# Relay-Board_Rack-PDU.net
KiCad netlist of a schematic drawn in EAGLE
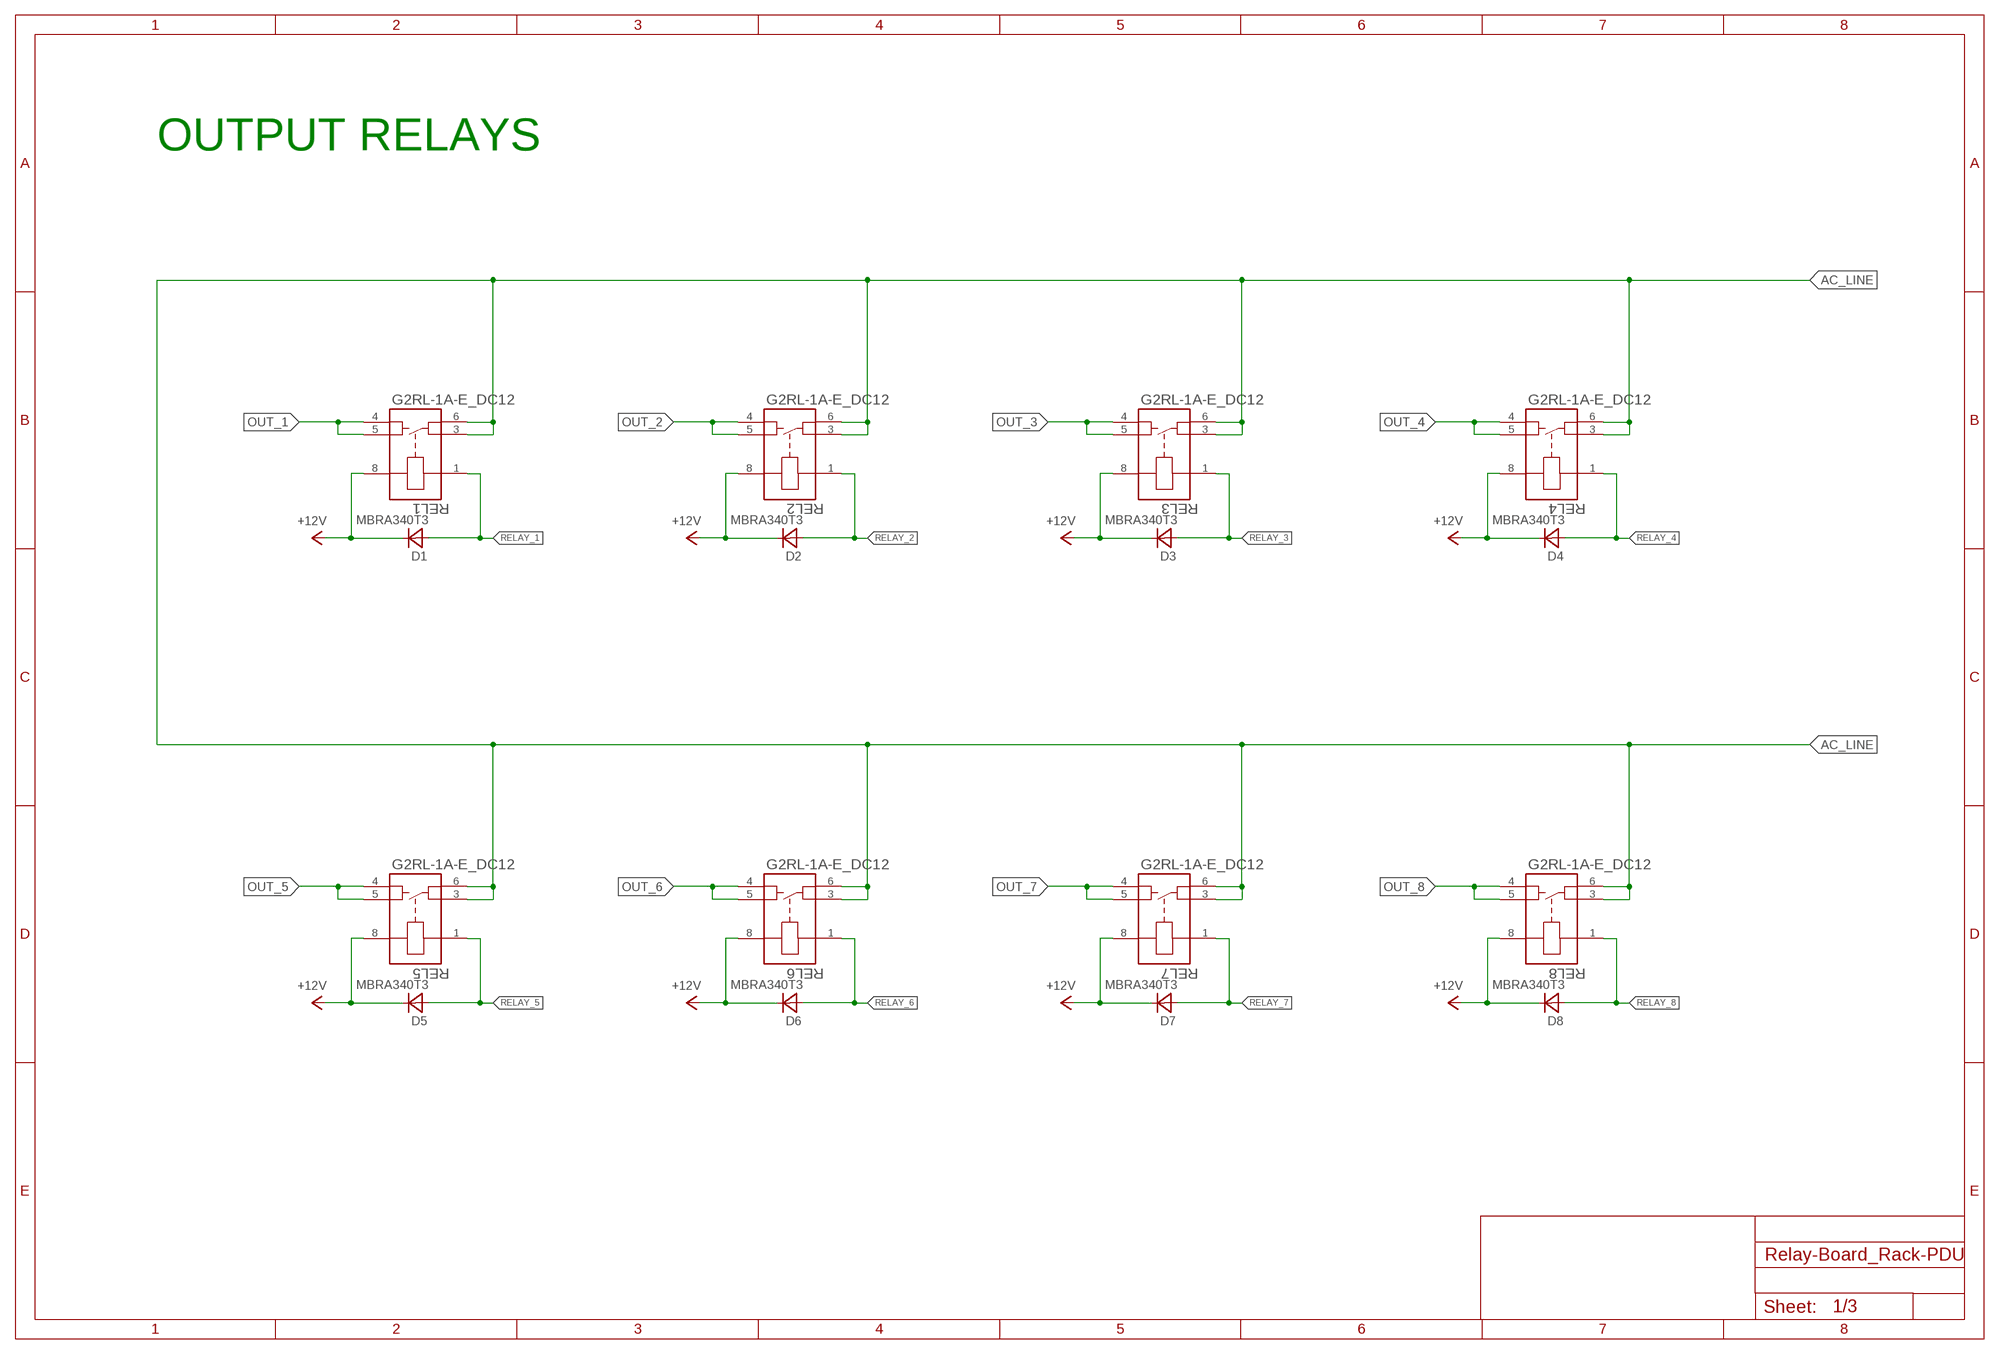
[diagram p0: schematic, sheet 1]
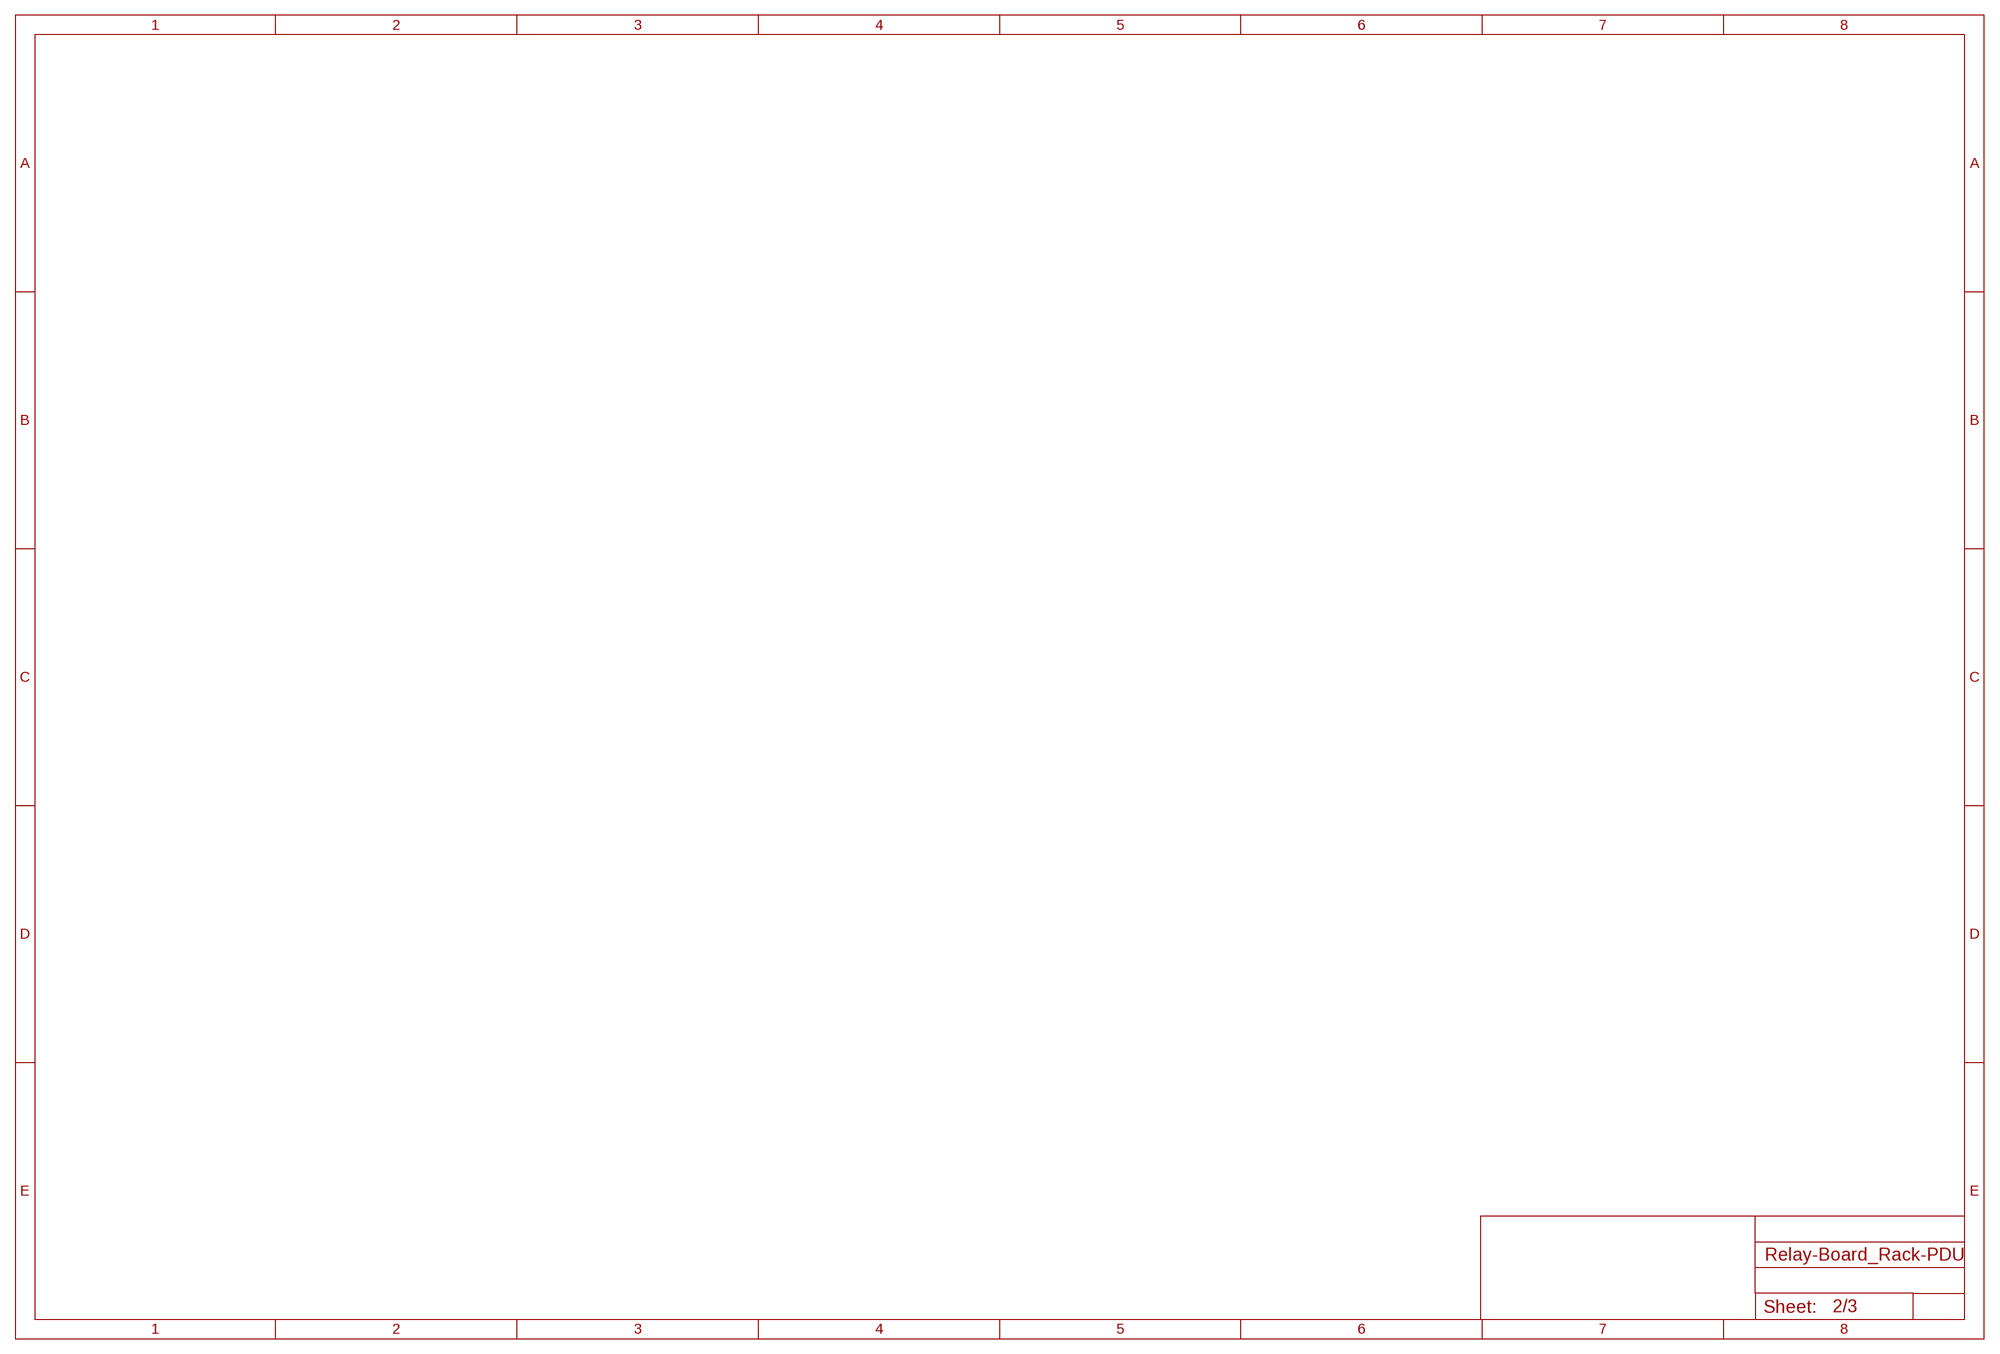
[diagram p1: schematic, sheet 2]
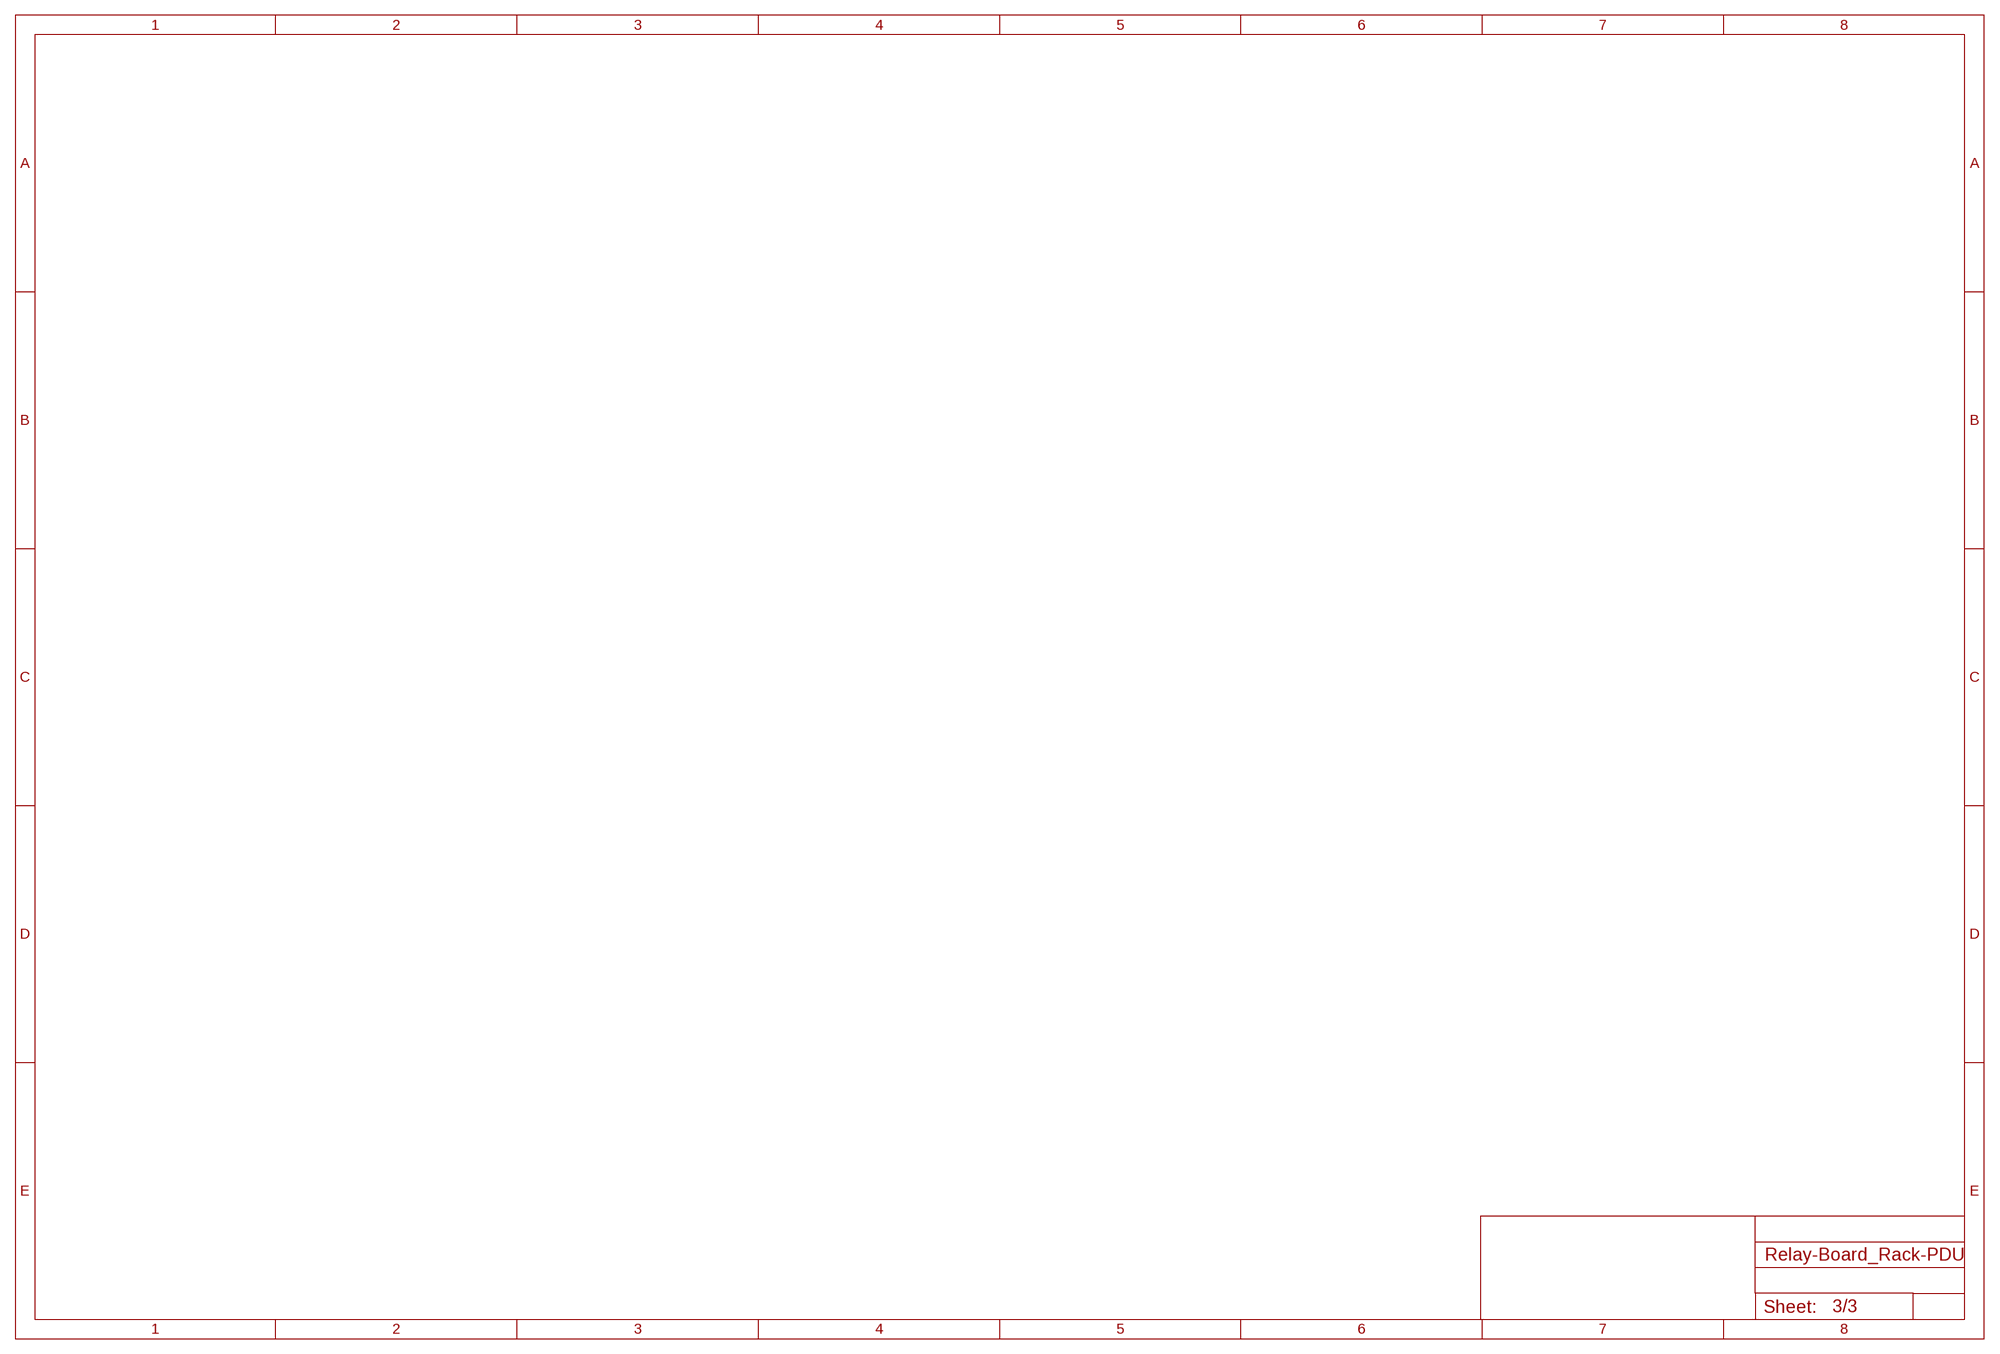
[diagram p2: schematic, sheet 3]

(export (version "E")
  (design (tool "Eeschema 10.0.6"))
  (components
    (comp (ref "D1")
      (value "MBRA340T3")
      (footprint "eagle-import:SMA")
      (libsource (lib "eagle-import") (part "MBRA340T3"))
    )
    (comp (ref "D2")
      (value "MBRA340T3")
      (footprint "eagle-import:SMA")
      (libsource (lib "eagle-import") (part "MBRA340T3"))
    )
    (comp (ref "D3")
      (value "MBRA340T3")
      (footprint "eagle-import:SMA")
      (libsource (lib "eagle-import") (part "MBRA340T3"))
    )
    (comp (ref "D4")
      (value "MBRA340T3")
      (footprint "eagle-import:SMA")
      (libsource (lib "eagle-import") (part "MBRA340T3"))
    )
    (comp (ref "D5")
      (value "MBRA340T3")
      (footprint "eagle-import:SMA")
      (libsource (lib "eagle-import") (part "MBRA340T3"))
    )
    (comp (ref "D6")
      (value "MBRA340T3")
      (footprint "eagle-import:SMA")
      (libsource (lib "eagle-import") (part "MBRA340T3"))
    )
    (comp (ref "D7")
      (value "MBRA340T3")
      (footprint "eagle-import:SMA")
      (libsource (lib "eagle-import") (part "MBRA340T3"))
    )
    (comp (ref "D8")
      (value "MBRA340T3")
      (footprint "eagle-import:SMA")
      (libsource (lib "eagle-import") (part "MBRA340T3"))
    )
    (comp (ref "REL1")
      (value "G2RL-1A-E_DC12")
      (footprint "eagle-import:RELAY_G2RL-1A-E_DC5_OMR")
      (fields
        (field (name "MANUFACTURER_PART_NUMBER") "G2RL-1A-E DC12")
        (field (name "COPYRIGHT") "Copyright (C) 2025 Ultra Librarian. All rights reserved.")
      )
      (libsource (lib "eagle-import") (part "G2RL-1A-E_DC12"))
    )
    (comp (ref "REL2")
      (value "G2RL-1A-E_DC12")
      (footprint "eagle-import:RELAY_G2RL-1A-E_DC5_OMR")
      (fields
        (field (name "MANUFACTURER_PART_NUMBER") "G2RL-1A-E DC12")
        (field (name "COPYRIGHT") "Copyright (C) 2025 Ultra Librarian. All rights reserved.")
      )
      (libsource (lib "eagle-import") (part "G2RL-1A-E_DC12"))
    )
    (comp (ref "REL3")
      (value "G2RL-1A-E_DC12")
      (footprint "eagle-import:RELAY_G2RL-1A-E_DC5_OMR")
      (fields
        (field (name "MANUFACTURER_PART_NUMBER") "G2RL-1A-E DC12")
        (field (name "COPYRIGHT") "Copyright (C) 2025 Ultra Librarian. All rights reserved.")
      )
      (libsource (lib "eagle-import") (part "G2RL-1A-E_DC12"))
    )
    (comp (ref "REL4")
      (value "G2RL-1A-E_DC12")
      (footprint "eagle-import:RELAY_G2RL-1A-E_DC5_OMR")
      (fields
        (field (name "MANUFACTURER_PART_NUMBER") "G2RL-1A-E DC12")
        (field (name "COPYRIGHT") "Copyright (C) 2025 Ultra Librarian. All rights reserved.")
      )
      (libsource (lib "eagle-import") (part "G2RL-1A-E_DC12"))
    )
    (comp (ref "REL5")
      (value "G2RL-1A-E_DC12")
      (footprint "eagle-import:RELAY_G2RL-1A-E_DC5_OMR")
      (fields
        (field (name "MANUFACTURER_PART_NUMBER") "G2RL-1A-E DC12")
        (field (name "COPYRIGHT") "Copyright (C) 2025 Ultra Librarian. All rights reserved.")
      )
      (libsource (lib "eagle-import") (part "G2RL-1A-E_DC12"))
    )
    (comp (ref "REL6")
      (value "G2RL-1A-E_DC12")
      (footprint "eagle-import:RELAY_G2RL-1A-E_DC5_OMR")
      (fields
        (field (name "MANUFACTURER_PART_NUMBER") "G2RL-1A-E DC12")
        (field (name "COPYRIGHT") "Copyright (C) 2025 Ultra Librarian. All rights reserved.")
      )
      (libsource (lib "eagle-import") (part "G2RL-1A-E_DC12"))
    )
    (comp (ref "REL7")
      (value "G2RL-1A-E_DC12")
      (footprint "eagle-import:RELAY_G2RL-1A-E_DC5_OMR")
      (fields
        (field (name "MANUFACTURER_PART_NUMBER") "G2RL-1A-E DC12")
        (field (name "COPYRIGHT") "Copyright (C) 2025 Ultra Librarian. All rights reserved.")
      )
      (libsource (lib "eagle-import") (part "G2RL-1A-E_DC12"))
    )
    (comp (ref "REL8")
      (value "G2RL-1A-E_DC12")
      (footprint "eagle-import:RELAY_G2RL-1A-E_DC5_OMR")
      (fields
        (field (name "MANUFACTURER_PART_NUMBER") "G2RL-1A-E DC12")
        (field (name "COPYRIGHT") "Copyright (C) 2025 Ultra Librarian. All rights reserved.")
      )
      (libsource (lib "eagle-import") (part "G2RL-1A-E_DC12"))
    )
  )
  (nets
    (net (code "1") (name "+12V") (class "Default")
      (node (ref "D1") (pin "C") (pinfunction "C_C") (pintype "passive"))
      (node (ref "D2") (pin "C") (pinfunction "C_C") (pintype "passive"))
      (node (ref "D3") (pin "C") (pinfunction "C_C") (pintype "passive"))
      (node (ref "D4") (pin "C") (pinfunction "C_C") (pintype "passive"))
      (node (ref "D5") (pin "C") (pinfunction "C_C") (pintype "passive"))
      (node (ref "D6") (pin "C") (pinfunction "C_C") (pintype "passive"))
      (node (ref "D7") (pin "C") (pinfunction "C_C") (pintype "passive"))
      (node (ref "D8") (pin "C") (pinfunction "C_C") (pintype "passive"))
      (node (ref "REL1") (pin "8") (pinfunction "8_8") (pintype "passive"))
      (node (ref "REL2") (pin "8") (pinfunction "8_8") (pintype "passive"))
      (node (ref "REL3") (pin "8") (pinfunction "8_8") (pintype "passive"))
      (node (ref "REL4") (pin "8") (pinfunction "8_8") (pintype "passive"))
      (node (ref "REL5") (pin "8") (pinfunction "8_8") (pintype "passive"))
      (node (ref "REL6") (pin "8") (pinfunction "8_8") (pintype "passive"))
      (node (ref "REL7") (pin "8") (pinfunction "8_8") (pintype "passive"))
      (node (ref "REL8") (pin "8") (pinfunction "8_8") (pintype "passive"))
    )
    (net (code "2") (name "AC_LINE") (class "Default")
      (node (ref "REL1") (pin "3") (pinfunction "3_3") (pintype "passive"))
      (node (ref "REL1") (pin "6") (pinfunction "6_6") (pintype "passive"))
      (node (ref "REL2") (pin "3") (pinfunction "3_3") (pintype "passive"))
      (node (ref "REL2") (pin "6") (pinfunction "6_6") (pintype "passive"))
      (node (ref "REL3") (pin "3") (pinfunction "3_3") (pintype "passive"))
      (node (ref "REL3") (pin "6") (pinfunction "6_6") (pintype "passive"))
      (node (ref "REL4") (pin "3") (pinfunction "3_3") (pintype "passive"))
      (node (ref "REL4") (pin "6") (pinfunction "6_6") (pintype "passive"))
      (node (ref "REL5") (pin "3") (pinfunction "3_3") (pintype "passive"))
      (node (ref "REL5") (pin "6") (pinfunction "6_6") (pintype "passive"))
      (node (ref "REL6") (pin "3") (pinfunction "3_3") (pintype "passive"))
      (node (ref "REL6") (pin "6") (pinfunction "6_6") (pintype "passive"))
      (node (ref "REL7") (pin "3") (pinfunction "3_3") (pintype "passive"))
      (node (ref "REL7") (pin "6") (pinfunction "6_6") (pintype "passive"))
      (node (ref "REL8") (pin "3") (pinfunction "3_3") (pintype "passive"))
      (node (ref "REL8") (pin "6") (pinfunction "6_6") (pintype "passive"))
    )
    (net (code "3") (name "OUT_1") (class "Default")
      (node (ref "REL1") (pin "4") (pinfunction "4_4") (pintype "passive"))
      (node (ref "REL1") (pin "5") (pinfunction "5_5") (pintype "passive"))
    )
    (net (code "4") (name "OUT_2") (class "Default")
      (node (ref "REL2") (pin "4") (pinfunction "4_4") (pintype "passive"))
      (node (ref "REL2") (pin "5") (pinfunction "5_5") (pintype "passive"))
    )
    (net (code "5") (name "OUT_3") (class "Default")
      (node (ref "REL3") (pin "4") (pinfunction "4_4") (pintype "passive"))
      (node (ref "REL3") (pin "5") (pinfunction "5_5") (pintype "passive"))
    )
    (net (code "6") (name "OUT_4") (class "Default")
      (node (ref "REL4") (pin "4") (pinfunction "4_4") (pintype "passive"))
      (node (ref "REL4") (pin "5") (pinfunction "5_5") (pintype "passive"))
    )
    (net (code "7") (name "OUT_5") (class "Default")
      (node (ref "REL5") (pin "4") (pinfunction "4_4") (pintype "passive"))
      (node (ref "REL5") (pin "5") (pinfunction "5_5") (pintype "passive"))
    )
    (net (code "8") (name "OUT_6") (class "Default")
      (node (ref "REL6") (pin "4") (pinfunction "4_4") (pintype "passive"))
      (node (ref "REL6") (pin "5") (pinfunction "5_5") (pintype "passive"))
    )
    (net (code "9") (name "OUT_7") (class "Default")
      (node (ref "REL7") (pin "4") (pinfunction "4_4") (pintype "passive"))
      (node (ref "REL7") (pin "5") (pinfunction "5_5") (pintype "passive"))
    )
    (net (code "10") (name "OUT_8") (class "Default")
      (node (ref "REL8") (pin "4") (pinfunction "4_4") (pintype "passive"))
      (node (ref "REL8") (pin "5") (pinfunction "5_5") (pintype "passive"))
    )
    (net (code "11") (name "RELAY_1") (class "Default")
      (node (ref "D1") (pin "A") (pinfunction "A_A") (pintype "passive"))
      (node (ref "REL1") (pin "1") (pinfunction "1_1") (pintype "passive"))
    )
    (net (code "12") (name "RELAY_2") (class "Default")
      (node (ref "D2") (pin "A") (pinfunction "A_A") (pintype "passive"))
      (node (ref "REL2") (pin "1") (pinfunction "1_1") (pintype "passive"))
    )
    (net (code "13") (name "RELAY_3") (class "Default")
      (node (ref "D3") (pin "A") (pinfunction "A_A") (pintype "passive"))
      (node (ref "REL3") (pin "1") (pinfunction "1_1") (pintype "passive"))
    )
    (net (code "14") (name "RELAY_4") (class "Default")
      (node (ref "D4") (pin "A") (pinfunction "A_A") (pintype "passive"))
      (node (ref "REL4") (pin "1") (pinfunction "1_1") (pintype "passive"))
    )
    (net (code "15") (name "RELAY_5") (class "Default")
      (node (ref "D5") (pin "A") (pinfunction "A_A") (pintype "passive"))
      (node (ref "REL5") (pin "1") (pinfunction "1_1") (pintype "passive"))
    )
    (net (code "16") (name "RELAY_6") (class "Default")
      (node (ref "D6") (pin "A") (pinfunction "A_A") (pintype "passive"))
      (node (ref "REL6") (pin "1") (pinfunction "1_1") (pintype "passive"))
    )
    (net (code "17") (name "RELAY_7") (class "Default")
      (node (ref "D7") (pin "A") (pinfunction "A_A") (pintype "passive"))
      (node (ref "REL7") (pin "1") (pinfunction "1_1") (pintype "passive"))
    )
    (net (code "18") (name "RELAY_8") (class "Default")
      (node (ref "D8") (pin "A") (pinfunction "A_A") (pintype "passive"))
      (node (ref "REL8") (pin "1") (pinfunction "1_1") (pintype "passive"))
    )
  )
)
